# EvapLITE.net
KiCad netlist of a schematic drawn in EAGLE
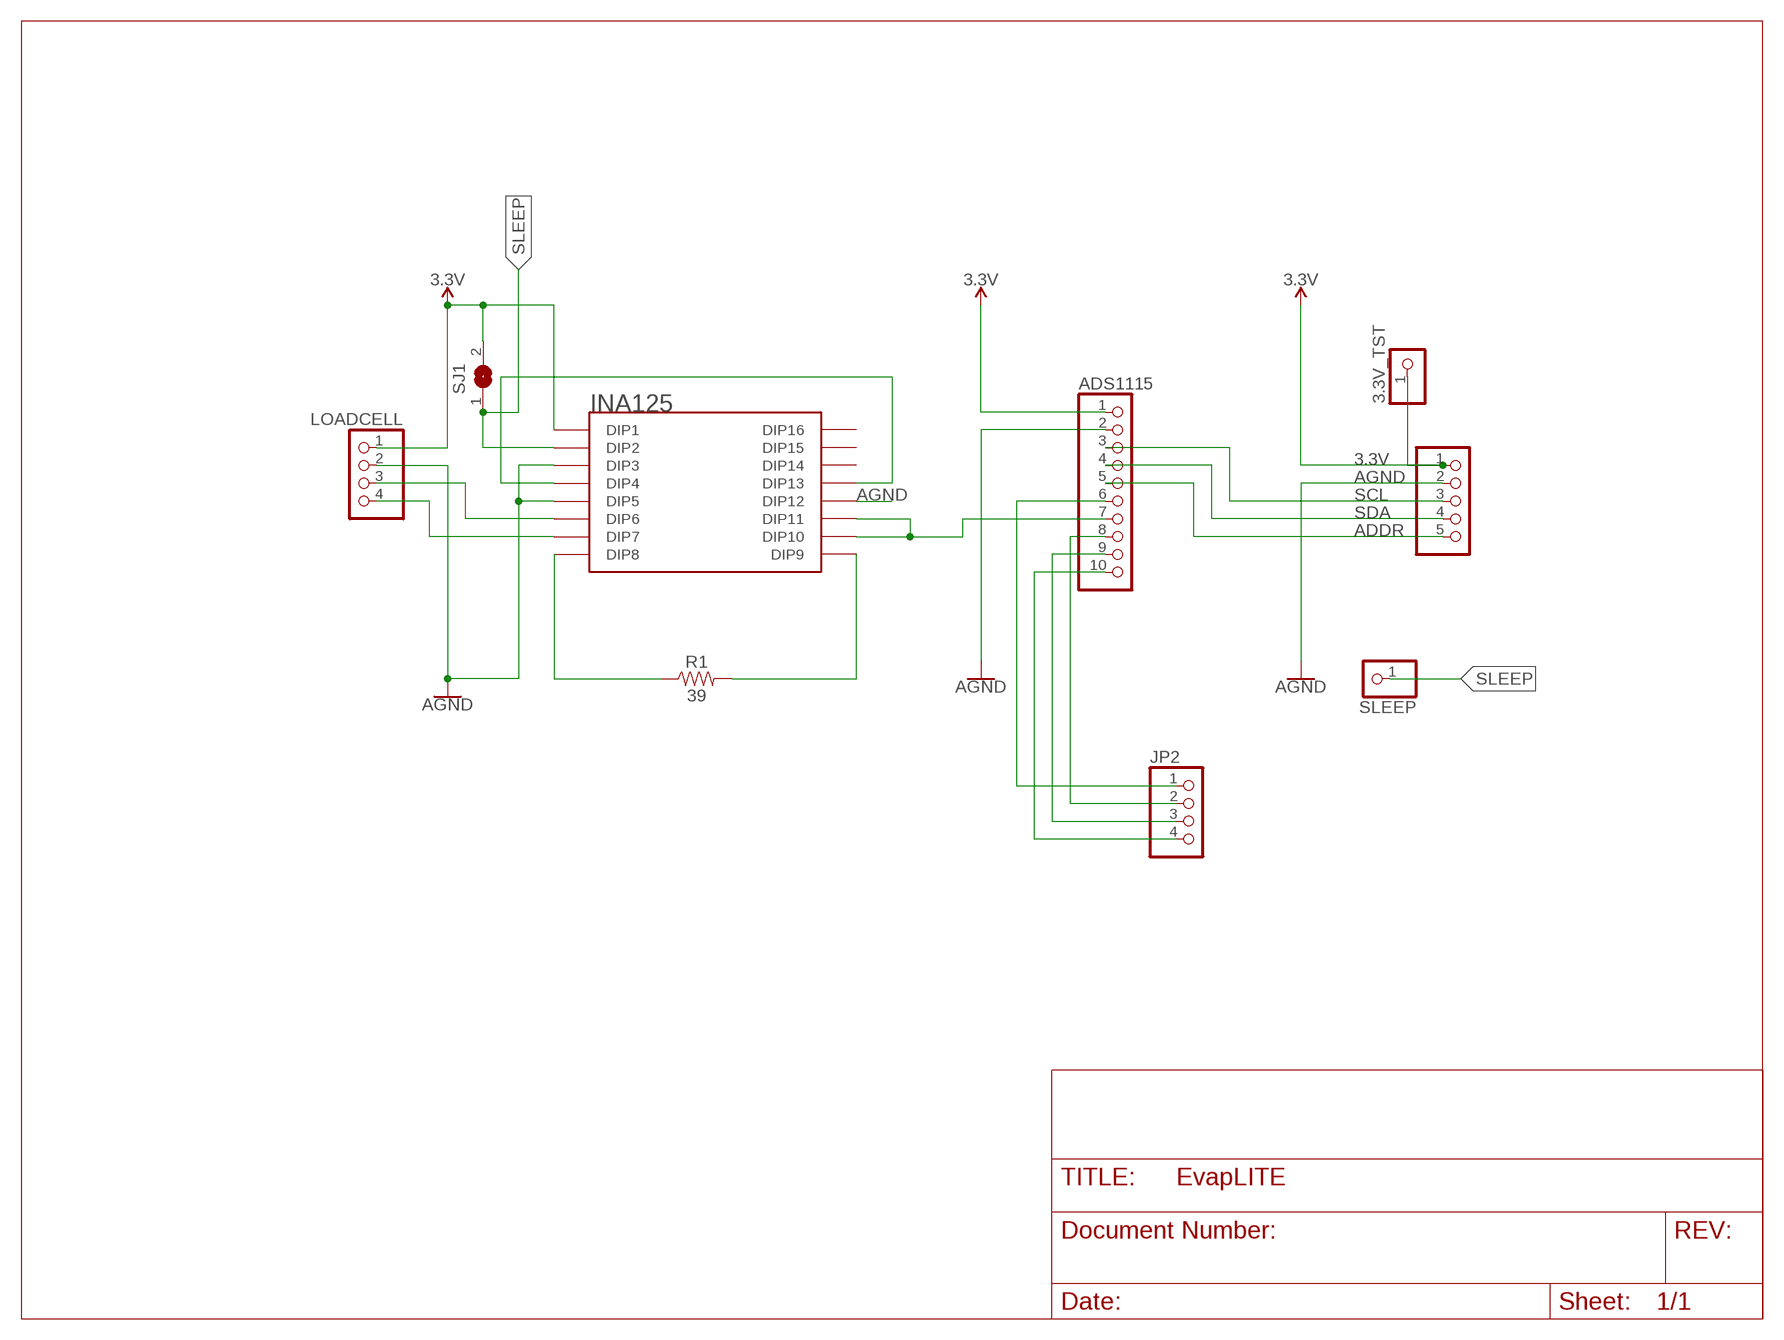
[diagram p0: schematic, sheet 1]

(export (version "E")
  (design (tool "Eeschema 10.0.6"))
  (components
    (comp (ref "3.3V_TST")
      (value "PINHD-1X1")
      (footprint "eagle-import:1X01")
      (libsource (lib "eagle-import") (part "PINHD-1X1"))
    )
    (comp (ref "ADS1115")
      (value "PINHD-1X10")
      (footprint "eagle-import:1X10")
      (libsource (lib "eagle-import") (part "PINHD-1X10"))
    )
    (comp (ref "I2C")
      (value "PINHD-1X5")
      (footprint "eagle-import:1X05")
      (libsource (lib "eagle-import") (part "PINHD-1X5"))
    )
    (comp (ref "INA125")
      (value "16-PIN_DIP")
      (footprint "eagle-import:16-PIN_DIP")
      (libsource (lib "eagle-import") (part "16-PIN_DIP"))
    )
    (comp (ref "JP2")
      (value "PINHD-1X4")
      (footprint "eagle-import:1X04")
      (libsource (lib "eagle-import") (part "PINHD-1X4"))
    )
    (comp (ref "LOADCELL")
      (value "PINHD-1X4")
      (footprint "eagle-import:1X04")
      (libsource (lib "eagle-import") (part "PINHD-1X4"))
    )
    (comp (ref "R1")
      (value "39")
      (footprint "eagle-import:AXIAL-0.3")
      (libsource (lib "eagle-import") (part "RESISTORAXIAL-0.3"))
    )
    (comp (ref "SJ1") (value "SJ") (footprint "eagle-import:SJ") (libsource (lib "eagle-import") (part "SJ")))
    (comp (ref "SLEEP")
      (value "PINHD-1X1")
      (footprint "eagle-import:1X01")
      (libsource (lib "eagle-import") (part "PINHD-1X1"))
    )
  )
  (nets
    (net (code "1") (name "/ADDR") (class "Default")
      (node (ref "ADS1115") (pin "5") (pinfunction "5_5") (pintype "passive"))
      (node (ref "I2C") (pin "5") (pinfunction "5_5") (pintype "passive"))
    )
    (net (code "2") (name "/SCL") (class "Default")
      (node (ref "ADS1115") (pin "3") (pinfunction "3_3") (pintype "passive"))
      (node (ref "I2C") (pin "3") (pinfunction "3_3") (pintype "passive"))
    )
    (net (code "3") (name "/SDA") (class "Default")
      (node (ref "ADS1115") (pin "4") (pinfunction "4_4") (pintype "passive"))
      (node (ref "I2C") (pin "4") (pinfunction "4_4") (pintype "passive"))
    )
    (net (code "4") (name "3.3V") (class "Default")
      (node (ref "3.3V_TST") (pin "1") (pinfunction "1_1") (pintype "passive"))
      (node (ref "ADS1115") (pin "1") (pinfunction "1_1") (pintype "passive"))
      (node (ref "I2C") (pin "1") (pinfunction "1_1") (pintype "passive"))
      (node (ref "INA125") (pin "DIP1") (pinfunction "DIP1_DIP1") (pintype "bidirectional"))
      (node (ref "LOADCELL") (pin "1") (pinfunction "1_1") (pintype "passive"))
      (node (ref "SJ1") (pin "2") (pinfunction "2_2") (pintype "passive"))
    )
    (net (code "5") (name "AGND") (class "Default")
      (node (ref "ADS1115") (pin "2") (pinfunction "2_2") (pintype "passive"))
      (node (ref "I2C") (pin "2") (pinfunction "2_2") (pintype "passive"))
      (node (ref "INA125") (pin "DIP12") (pinfunction "DIP12_DIP12") (pintype "bidirectional"))
      (node (ref "INA125") (pin "DIP3") (pinfunction "DIP3_DIP3") (pintype "bidirectional"))
      (node (ref "INA125") (pin "DIP5") (pinfunction "DIP5_DIP5") (pintype "bidirectional"))
      (node (ref "LOADCELL") (pin "2") (pinfunction "2_2") (pintype "passive"))
    )
    (net (code "6") (name "Net-(ADS1115-Pad6)") (class "Default")
      (node (ref "ADS1115") (pin "6") (pinfunction "6_6") (pintype "passive"))
      (node (ref "JP2") (pin "1") (pinfunction "1_1") (pintype "passive"))
    )
    (net (code "7") (name "Net-(ADS1115-Pad7)") (class "Default")
      (node (ref "ADS1115") (pin "7") (pinfunction "7_7") (pintype "passive"))
      (node (ref "INA125") (pin "DIP10") (pinfunction "DIP10_DIP10") (pintype "bidirectional"))
      (node (ref "INA125") (pin "DIP11") (pinfunction "DIP11_DIP11") (pintype "bidirectional"))
    )
    (net (code "8") (name "Net-(ADS1115-Pad8)") (class "Default")
      (node (ref "ADS1115") (pin "8") (pinfunction "8_8") (pintype "passive"))
      (node (ref "JP2") (pin "2") (pinfunction "2_2") (pintype "passive"))
    )
    (net (code "9") (name "Net-(ADS1115-Pad9)") (class "Default")
      (node (ref "ADS1115") (pin "9") (pinfunction "9_9") (pintype "passive"))
      (node (ref "JP2") (pin "3") (pinfunction "3_3") (pintype "passive"))
    )
    (net (code "10") (name "Net-(ADS1115-Pad10)") (class "Default")
      (node (ref "ADS1115") (pin "10") (pinfunction "10_10") (pintype "passive"))
      (node (ref "JP2") (pin "4") (pinfunction "4_4") (pintype "passive"))
    )
    (net (code "11") (name "Net-(INA125-PadDIP6)") (class "Default")
      (node (ref "INA125") (pin "DIP6") (pinfunction "DIP6_DIP6") (pintype "bidirectional"))
      (node (ref "LOADCELL") (pin "3") (pinfunction "3_3") (pintype "passive"))
    )
    (net (code "12") (name "Net-(INA125-PadDIP7)") (class "Default")
      (node (ref "INA125") (pin "DIP7") (pinfunction "DIP7_DIP7") (pintype "bidirectional"))
      (node (ref "LOADCELL") (pin "4") (pinfunction "4_4") (pintype "passive"))
    )
    (net (code "13") (name "Net-(INA125-PadDIP13)") (class "Default")
      (node (ref "INA125") (pin "DIP13") (pinfunction "DIP13_DIP13") (pintype "bidirectional"))
      (node (ref "INA125") (pin "DIP4") (pinfunction "DIP4_DIP4") (pintype "bidirectional"))
    )
    (net (code "14") (name "Net-(R1-1)") (class "Default")
      (node (ref "INA125") (pin "DIP8") (pinfunction "DIP8_DIP8") (pintype "bidirectional"))
      (node (ref "R1") (pin "P$1") (pinfunction "1_P$1") (pintype "passive"))
    )
    (net (code "15") (name "Net-(R1-2)") (class "Default")
      (node (ref "INA125") (pin "DIP9") (pinfunction "DIP9_DIP9") (pintype "bidirectional"))
      (node (ref "R1") (pin "P$2") (pinfunction "2_P$2") (pintype "passive"))
    )
    (net (code "16") (name "SLEEP") (class "Default")
      (node (ref "INA125") (pin "DIP2") (pinfunction "DIP2_DIP2") (pintype "bidirectional"))
      (node (ref "SJ1") (pin "1") (pinfunction "1_1") (pintype "passive"))
      (node (ref "SLEEP") (pin "1") (pinfunction "1_1") (pintype "passive"))
    )
    (net (code "17") (name "unconnected-(INA125-PadDIP14)") (class "Default")
      (node (ref "INA125") (pin "DIP14") (pinfunction "DIP14_DIP14") (pintype "bidirectional"))
    )
    (net (code "18") (name "unconnected-(INA125-PadDIP15)") (class "Default")
      (node (ref "INA125") (pin "DIP15") (pinfunction "DIP15_DIP15") (pintype "bidirectional"))
    )
    (net (code "19") (name "unconnected-(INA125-PadDIP16)") (class "Default")
      (node (ref "INA125") (pin "DIP16") (pinfunction "DIP16_DIP16") (pintype "bidirectional"))
    )
  )
)
